# Boss_HM-2.net
KiCad netlist of a schematic drawn in EAGLE
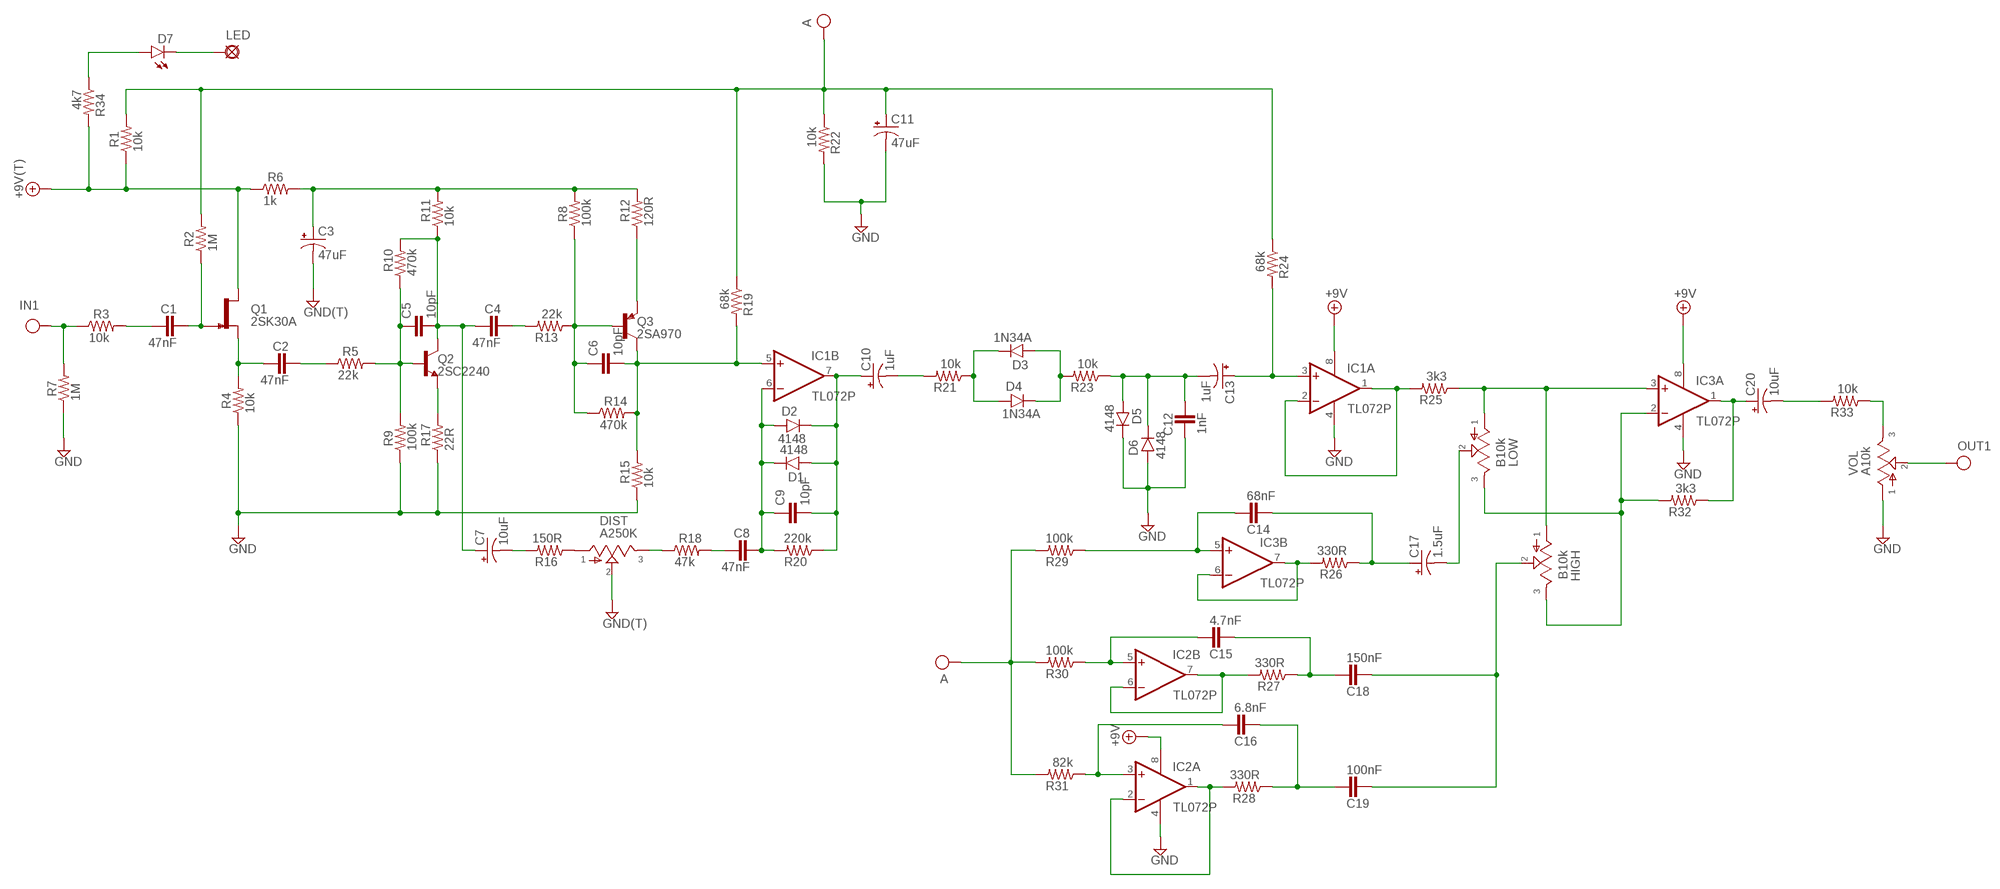
[diagram p0: schematic, sheet 1]

(export (version "E")
  (design (tool "Eeschema 10.0.6"))
  (components
    (comp (ref "+9V1")
      (value "+9V(T)")
      (footprint "eagle-import:SQUARE")
      (libsource (lib "eagle-import") (part "+9V(T)"))
    )
    (comp (ref "C1")
      (value "47nF")
      (footprint "eagle-import:072X025")
      (libsource (lib "eagle-import") (part "072X0252"))
    )
    (comp (ref "C2")
      (value "47nF")
      (footprint "eagle-import:072X025")
      (libsource (lib "eagle-import") (part "072X0252"))
    )
    (comp (ref "C3")
      (value "47uF")
      (footprint "eagle-import:050_020_1")
      (libsource (lib "eagle-import") (part "0501"))
    )
    (comp (ref "C4")
      (value "47nF")
      (footprint "eagle-import:072X025")
      (libsource (lib "eagle-import") (part "072X0252"))
    )
    (comp (ref "C5")
      (value "10pF")
      (footprint "eagle-import:050X030_025")
      (libsource (lib "eagle-import") (part "050X030_0251"))
    )
    (comp (ref "C6")
      (value "10pF")
      (footprint "eagle-import:050X030_025")
      (libsource (lib "eagle-import") (part "050X030_0251"))
    )
    (comp (ref "C7")
      (value "10uF")
      (footprint "eagle-import:050_020_1")
      (libsource (lib "eagle-import") (part "0501"))
    )
    (comp (ref "C8")
      (value "47nF")
      (footprint "eagle-import:072X025")
      (libsource (lib "eagle-import") (part "072X0252"))
    )
    (comp (ref "C9")
      (value "10pF")
      (footprint "eagle-import:050X030_025")
      (libsource (lib "eagle-import") (part "050X030_0251"))
    )
    (comp (ref "C10")
      (value "1uF")
      (footprint "eagle-import:050_020_1")
      (libsource (lib "eagle-import") (part "0501"))
    )
    (comp (ref "C11")
      (value "47uF")
      (footprint "eagle-import:050_020_1")
      (libsource (lib "eagle-import") (part "0501"))
    )
    (comp (ref "C12")
      (value "1nF")
      (footprint "eagle-import:072X025")
      (libsource (lib "eagle-import") (part "072X0252"))
    )
    (comp (ref "C13")
      (value "1uF")
      (footprint "eagle-import:050_020_1")
      (libsource (lib "eagle-import") (part "0501"))
    )
    (comp (ref "C14")
      (value "68nF")
      (footprint "eagle-import:072X025")
      (libsource (lib "eagle-import") (part "072X0252"))
    )
    (comp (ref "C15")
      (value "4.7nF")
      (footprint "eagle-import:072X025")
      (libsource (lib "eagle-import") (part "072X0252"))
    )
    (comp (ref "C16")
      (value "6.8nF")
      (footprint "eagle-import:072X025")
      (libsource (lib "eagle-import") (part "072X0252"))
    )
    (comp (ref "C17")
      (value "1.5uF")
      (footprint "eagle-import:050_020_1")
      (libsource (lib "eagle-import") (part "0501"))
    )
    (comp (ref "C18")
      (value "150nF")
      (footprint "eagle-import:072X025")
      (libsource (lib "eagle-import") (part "072X0252"))
    )
    (comp (ref "C19")
      (value "100nF")
      (footprint "eagle-import:072X025")
      (libsource (lib "eagle-import") (part "072X0252"))
    )
    (comp (ref "C20")
      (value "10uF")
      (footprint "eagle-import:050_020_1")
      (libsource (lib "eagle-import") (part "0501"))
    )
    (comp (ref "D1")
      (value "4148")
      (footprint "eagle-import:DO35-3")
      (libsource (lib "eagle-import") (part "1N4148-3"))
    )
    (comp (ref "D2")
      (value "4148")
      (footprint "eagle-import:DO35-3")
      (libsource (lib "eagle-import") (part "1N4148-3"))
    )
    (comp (ref "D3")
      (value "1N34A")
      (footprint "eagle-import:DO07")
      (libsource (lib "eagle-import") (part "DO07"))
    )
    (comp (ref "D4")
      (value "1N34A")
      (footprint "eagle-import:DO07")
      (libsource (lib "eagle-import") (part "DO07"))
    )
    (comp (ref "D5")
      (value "4148")
      (footprint "eagle-import:DO35-3")
      (libsource (lib "eagle-import") (part "1N4148-3"))
    )
    (comp (ref "D6")
      (value "4148")
      (footprint "eagle-import:DO35-3")
      (libsource (lib "eagle-import") (part "1N4148-3"))
    )
    (comp (ref "D7")
      (value "LED3MM")
      (footprint "eagle-import:LED3MM")
      (libsource (lib "eagle-import") (part "LED3MM"))
    )
    (comp (ref "DIST")
      (value "A250K")
      (footprint "eagle-import:16MM_PCB_PADS")
      (libsource (lib "eagle-import") (part "POT16MM_PCB_PADS"))
    )
    (comp (ref "GND1")
      (value "GND(T)")
      (footprint "eagle-import:SQUARE")
      (libsource (lib "eagle-import") (part "GND(T)"))
    )
    (comp (ref "GND2")
      (value "GND(T)")
      (footprint "eagle-import:SQUARE")
      (libsource (lib "eagle-import") (part "GND(T)"))
    )
    (comp (ref "HIGH")
      (value "B10k")
      (footprint "eagle-import:16MM_PCB_PADS")
      (libsource (lib "eagle-import") (part "POT16MM_PCB_PADS"))
    )
    (comp (ref "IC1")
      (value "TL072P")
      (footprint "eagle-import:DIL08")
      (libsource (lib "eagle-import") (part "TL072P"))
    )
    (comp (ref "IC2")
      (value "TL072P")
      (footprint "eagle-import:DIL08")
      (libsource (lib "eagle-import") (part "TL072P"))
    )
    (comp (ref "IC3")
      (value "TL072P")
      (footprint "eagle-import:DIL08")
      (libsource (lib "eagle-import") (part "TL072P"))
    )
    (comp (ref "IN1")
      (value "IN(T)")
      (footprint "eagle-import:SQUARE")
      (libsource (lib "eagle-import") (part "IN(T)"))
    )
    (comp (ref "LED")
      (value "PAD")
      (footprint "eagle-import:SQUARE")
      (libsource (lib "eagle-import") (part "PAD"))
    )
    (comp (ref "LOW")
      (value "B10k")
      (footprint "eagle-import:16MM_PCB_PADS")
      (libsource (lib "eagle-import") (part "POT16MM_PCB_PADS"))
    )
    (comp (ref "OUT1")
      (value "OUT(T)")
      (footprint "eagle-import:SQUARE")
      (libsource (lib "eagle-import") (part "OUT(T)"))
    )
    (comp (ref "Q1")
      (value "2SK30A")
      (footprint "eagle-import:TO92-")
      (libsource (lib "eagle-import") (part "2SK30A"))
    )
    (comp (ref "Q2")
      (value "2SC2240")
      (footprint "eagle-import:TO92-")
      (libsource (lib "eagle-import") (part "2N5089"))
    )
    (comp (ref "Q3")
      (value "2SA970")
      (footprint "eagle-import:TO92-")
      (libsource (lib "eagle-import") (part "2SA733"))
    )
    (comp (ref "R1")
      (value "10k")
      (footprint "eagle-import:R0207_3")
      (libsource (lib "eagle-import") (part "6MM.3"))
    )
    (comp (ref "R2")
      (value "1M")
      (footprint "eagle-import:R0207_3")
      (libsource (lib "eagle-import") (part "6MM.3"))
    )
    (comp (ref "R3")
      (value "10k")
      (footprint "eagle-import:R0207_3")
      (libsource (lib "eagle-import") (part "6MM.3"))
    )
    (comp (ref "R4")
      (value "10k")
      (footprint "eagle-import:R0207_3")
      (libsource (lib "eagle-import") (part "6MM.3"))
    )
    (comp (ref "R5")
      (value "22k")
      (footprint "eagle-import:R0207_3")
      (libsource (lib "eagle-import") (part "6MM.3"))
    )
    (comp (ref "R6")
      (value "1k")
      (footprint "eagle-import:R0207_3")
      (libsource (lib "eagle-import") (part "6MM.3"))
    )
    (comp (ref "R7")
      (value "1M")
      (footprint "eagle-import:R0207_3")
      (libsource (lib "eagle-import") (part "6MM.3"))
    )
    (comp (ref "R8")
      (value "100k")
      (footprint "eagle-import:R0207_3")
      (libsource (lib "eagle-import") (part "6MM.3"))
    )
    (comp (ref "R9")
      (value "100k")
      (footprint "eagle-import:R0207_3")
      (libsource (lib "eagle-import") (part "6MM.3"))
    )
    (comp (ref "R10")
      (value "470k")
      (footprint "eagle-import:R0207_3")
      (libsource (lib "eagle-import") (part "6MM.3"))
    )
    (comp (ref "R11")
      (value "10k")
      (footprint "eagle-import:R0207_3")
      (libsource (lib "eagle-import") (part "6MM.3"))
    )
    (comp (ref "R12")
      (value "120R")
      (footprint "eagle-import:R0207_3")
      (libsource (lib "eagle-import") (part "6MM.3"))
    )
    (comp (ref "R13")
      (value "22k")
      (footprint "eagle-import:R0207_3")
      (libsource (lib "eagle-import") (part "6MM.3"))
    )
    (comp (ref "R14")
      (value "470k")
      (footprint "eagle-import:R0207_3")
      (libsource (lib "eagle-import") (part "6MM.3"))
    )
    (comp (ref "R15")
      (value "10k")
      (footprint "eagle-import:R0207_3")
      (libsource (lib "eagle-import") (part "6MM.3"))
    )
    (comp (ref "R16")
      (value "150R")
      (footprint "eagle-import:R0207_3")
      (libsource (lib "eagle-import") (part "6MM.3"))
    )
    (comp (ref "R17")
      (value "22R")
      (footprint "eagle-import:R0207_3")
      (libsource (lib "eagle-import") (part "6MM.3"))
    )
    (comp (ref "R18")
      (value "47k")
      (footprint "eagle-import:R0207_3")
      (libsource (lib "eagle-import") (part "6MM.3"))
    )
    (comp (ref "R19")
      (value "68k")
      (footprint "eagle-import:R0207_3")
      (libsource (lib "eagle-import") (part "6MM.3"))
    )
    (comp (ref "R20")
      (value "220k")
      (footprint "eagle-import:R0207_3")
      (libsource (lib "eagle-import") (part "6MM.3"))
    )
    (comp (ref "R21")
      (value "10k")
      (footprint "eagle-import:R0207_3")
      (libsource (lib "eagle-import") (part "6MM.3"))
    )
    (comp (ref "R22")
      (value "10k")
      (footprint "eagle-import:R0207_3")
      (libsource (lib "eagle-import") (part "6MM.3"))
    )
    (comp (ref "R23")
      (value "10k")
      (footprint "eagle-import:R0207_3")
      (libsource (lib "eagle-import") (part "6MM.3"))
    )
    (comp (ref "R24")
      (value "68k")
      (footprint "eagle-import:R0207_3")
      (libsource (lib "eagle-import") (part "6MM.3"))
    )
    (comp (ref "R25")
      (value "3k3")
      (footprint "eagle-import:R0207_3")
      (libsource (lib "eagle-import") (part "6MM.3"))
    )
    (comp (ref "R26")
      (value "330R")
      (footprint "eagle-import:R0207_3")
      (libsource (lib "eagle-import") (part "6MM.3"))
    )
    (comp (ref "R27")
      (value "330R")
      (footprint "eagle-import:R0207_3")
      (libsource (lib "eagle-import") (part "6MM.3"))
    )
    (comp (ref "R28")
      (value "330R")
      (footprint "eagle-import:R0207_3")
      (libsource (lib "eagle-import") (part "6MM.3"))
    )
    (comp (ref "R29")
      (value "100k")
      (footprint "eagle-import:R0207_3")
      (libsource (lib "eagle-import") (part "6MM.3"))
    )
    (comp (ref "R30")
      (value "100k")
      (footprint "eagle-import:R0207_3")
      (libsource (lib "eagle-import") (part "6MM.3"))
    )
    (comp (ref "R31")
      (value "82k")
      (footprint "eagle-import:R0207_3")
      (libsource (lib "eagle-import") (part "6MM.3"))
    )
    (comp (ref "R32")
      (value "3k3")
      (footprint "eagle-import:R0207_3")
      (libsource (lib "eagle-import") (part "6MM.3"))
    )
    (comp (ref "R33")
      (value "10k")
      (footprint "eagle-import:R0207_3")
      (libsource (lib "eagle-import") (part "6MM.3"))
    )
    (comp (ref "R34")
      (value "4k7")
      (footprint "eagle-import:R0207_3")
      (libsource (lib "eagle-import") (part "6MM.3"))
    )
    (comp (ref "VOL")
      (value "A10k")
      (footprint "eagle-import:16MM_PCB_PADS")
      (libsource (lib "eagle-import") (part "POT16MM_PCB_PADS"))
    )
  )
  (nets
    (net (code "1") (name "+9V") (class "Default")
      (node (ref "+9V1") (pin "1") (pinfunction "+9V_1") (pintype "power_in"))
      (node (ref "IC1") (pin "8") (pinfunction "V+_8") (pintype "power_in"))
      (node (ref "IC2") (pin "8") (pinfunction "V+_8") (pintype "power_in"))
      (node (ref "IC3") (pin "8") (pinfunction "V+_8") (pintype "power_in"))
      (node (ref "Q1") (pin "3") (pinfunction "D_3") (pintype "passive"))
      (node (ref "R1") (pin "1") (pinfunction "1_1") (pintype "passive"))
      (node (ref "R34") (pin "2") (pinfunction "2_2") (pintype "passive"))
      (node (ref "R6") (pin "1") (pinfunction "1_1") (pintype "passive"))
    )
    (net (code "2") (name "A") (class "Default")
      (node (ref "C11") (pin "+") (pinfunction "+_+") (pintype "passive"))
      (node (ref "R1") (pin "2") (pinfunction "2_2") (pintype "passive"))
      (node (ref "R19") (pin "1") (pinfunction "1_1") (pintype "passive"))
      (node (ref "R2") (pin "2") (pinfunction "2_2") (pintype "passive"))
      (node (ref "R22") (pin "1") (pinfunction "1_1") (pintype "passive"))
      (node (ref "R24") (pin "1") (pinfunction "1_1") (pintype "passive"))
      (node (ref "R29") (pin "2") (pinfunction "2_2") (pintype "passive"))
      (node (ref "R30") (pin "2") (pinfunction "2_2") (pintype "passive"))
      (node (ref "R31") (pin "2") (pinfunction "2_2") (pintype "passive"))
    )
    (net (code "3") (name "GND") (class "Default")
      (node (ref "C11") (pin "-") (pinfunction "-_-") (pintype "passive"))
      (node (ref "C12") (pin "1") (pinfunction "1_1") (pintype "passive"))
      (node (ref "C3") (pin "-") (pinfunction "-_-") (pintype "passive"))
      (node (ref "D5") (pin "C") (pinfunction "C_C") (pintype "passive"))
      (node (ref "D6") (pin "A") (pinfunction "A_A") (pintype "passive"))
      (node (ref "DIST") (pin "2") (pinfunction "2_2") (pintype "passive"))
      (node (ref "GND1") (pin "1") (pinfunction "GND_1") (pintype "power_in"))
      (node (ref "GND2") (pin "1") (pinfunction "GND_1") (pintype "power_in"))
      (node (ref "IC1") (pin "4") (pinfunction "V-_4") (pintype "power_in"))
      (node (ref "IC2") (pin "4") (pinfunction "V-_4") (pintype "power_in"))
      (node (ref "IC3") (pin "4") (pinfunction "V-_4") (pintype "power_in"))
      (node (ref "R15") (pin "1") (pinfunction "1_1") (pintype "passive"))
      (node (ref "R17") (pin "1") (pinfunction "1_1") (pintype "passive"))
      (node (ref "R22") (pin "2") (pinfunction "2_2") (pintype "passive"))
      (node (ref "R4") (pin "1") (pinfunction "1_1") (pintype "passive"))
      (node (ref "R7") (pin "1") (pinfunction "1_1") (pintype "passive"))
      (node (ref "R9") (pin "1") (pinfunction "1_1") (pintype "passive"))
      (node (ref "VOL") (pin "1") (pinfunction "1_1") (pintype "passive"))
    )
    (net (code "4") (name "IN(T)") (class "Default")
      (node (ref "IN1") (pin "1") (pinfunction "IN_1") (pintype "power_in"))
      (node (ref "R3") (pin "1") (pinfunction "1_1") (pintype "passive"))
      (node (ref "R7") (pin "2") (pinfunction "2_2") (pintype "passive"))
    )
    (net (code "5") (name "Net-(C1-Pad1)") (class "Default")
      (node (ref "C1") (pin "1") (pinfunction "1_1") (pintype "passive"))
      (node (ref "R3") (pin "2") (pinfunction "2_2") (pintype "passive"))
    )
    (net (code "6") (name "Net-(C2-Pad2)") (class "Default")
      (node (ref "C2") (pin "2") (pinfunction "2_2") (pintype "passive"))
      (node (ref "R5") (pin "1") (pinfunction "1_1") (pintype "passive"))
    )
    (net (code "7") (name "Net-(C3-Pad+)") (class "Default")
      (node (ref "C3") (pin "+") (pinfunction "+_+") (pintype "passive"))
      (node (ref "R11") (pin "2") (pinfunction "2_2") (pintype "passive"))
      (node (ref "R12") (pin "2") (pinfunction "2_2") (pintype "passive"))
      (node (ref "R6") (pin "2") (pinfunction "2_2") (pintype "passive"))
      (node (ref "R8") (pin "2") (pinfunction "2_2") (pintype "passive"))
    )
    (net (code "8") (name "Net-(C4-Pad2)") (class "Default")
      (node (ref "C4") (pin "2") (pinfunction "2_2") (pintype "passive"))
      (node (ref "R13") (pin "2") (pinfunction "2_2") (pintype "passive"))
    )
    (net (code "9") (name "Net-(C7-Pad-)") (class "Default")
      (node (ref "C7") (pin "-") (pinfunction "-_-") (pintype "passive"))
      (node (ref "R16") (pin "2") (pinfunction "2_2") (pintype "passive"))
    )
    (net (code "10") (name "Net-(C8-Pad1)") (class "Default")
      (node (ref "C8") (pin "1") (pinfunction "1_1") (pintype "passive"))
      (node (ref "R18") (pin "2") (pinfunction "2_2") (pintype "passive"))
    )
    (net (code "11") (name "Net-(C10-Pad-)") (class "Default")
      (node (ref "C10") (pin "-") (pinfunction "-_-") (pintype "passive"))
      (node (ref "R21") (pin "2") (pinfunction "2_2") (pintype "passive"))
    )
    (net (code "12") (name "Net-(C12-Pad2)") (class "Default")
      (node (ref "C12") (pin "2") (pinfunction "2_2") (pintype "passive"))
      (node (ref "C13") (pin "-") (pinfunction "-_-") (pintype "passive"))
      (node (ref "D5") (pin "A") (pinfunction "A_A") (pintype "passive"))
      (node (ref "D6") (pin "C") (pinfunction "C_C") (pintype "passive"))
      (node (ref "R23") (pin "1") (pinfunction "1_1") (pintype "passive"))
    )
    (net (code "13") (name "Net-(C14-Pad1)") (class "Default")
      (node (ref "C14") (pin "1") (pinfunction "1_1") (pintype "passive"))
      (node (ref "C17") (pin "+") (pinfunction "+_+") (pintype "passive"))
      (node (ref "R26") (pin "1") (pinfunction "1_1") (pintype "passive"))
    )
    (net (code "14") (name "Net-(C15-Pad1)") (class "Default")
      (node (ref "C15") (pin "1") (pinfunction "1_1") (pintype "passive"))
      (node (ref "C18") (pin "2") (pinfunction "2_2") (pintype "passive"))
      (node (ref "R27") (pin "1") (pinfunction "1_1") (pintype "passive"))
    )
    (net (code "15") (name "Net-(C16-Pad1)") (class "Default")
      (node (ref "C16") (pin "1") (pinfunction "1_1") (pintype "passive"))
      (node (ref "C19") (pin "2") (pinfunction "2_2") (pintype "passive"))
      (node (ref "R28") (pin "1") (pinfunction "1_1") (pintype "passive"))
    )
    (net (code "16") (name "Net-(C17-Pad-)") (class "Default")
      (node (ref "C17") (pin "-") (pinfunction "-_-") (pintype "passive"))
      (node (ref "LOW") (pin "2") (pinfunction "2_2") (pintype "passive"))
    )
    (net (code "17") (name "Net-(C18-Pad1)") (class "Default")
      (node (ref "C18") (pin "1") (pinfunction "1_1") (pintype "passive"))
      (node (ref "C19") (pin "1") (pinfunction "1_1") (pintype "passive"))
      (node (ref "HIGH") (pin "2") (pinfunction "2_2") (pintype "passive"))
    )
    (net (code "18") (name "Net-(C20-Pad-)") (class "Default")
      (node (ref "C20") (pin "-") (pinfunction "-_-") (pintype "passive"))
      (node (ref "R33") (pin "2") (pinfunction "2_2") (pintype "passive"))
    )
    (net (code "19") (name "Net-(D3-PadA)") (class "Default")
      (node (ref "D3") (pin "A") (pinfunction "A_A") (pintype "passive"))
      (node (ref "D4") (pin "C") (pinfunction "C_C") (pintype "passive"))
      (node (ref "R23") (pin "2") (pinfunction "2_2") (pintype "passive"))
    )
    (net (code "20") (name "Net-(D3-PadC)") (class "Default")
      (node (ref "D3") (pin "C") (pinfunction "C_C") (pintype "passive"))
      (node (ref "D4") (pin "A") (pinfunction "A_A") (pintype "passive"))
      (node (ref "R21") (pin "1") (pinfunction "1_1") (pintype "passive"))
    )
    (net (code "21") (name "Net-(D7-C)") (class "Default")
      (node (ref "D7") (pin "K") (pinfunction "C_K") (pintype "passive"))
      (node (ref "LED") (pin "1") (pinfunction "PAD_1") (pintype "passive"))
    )
    (net (code "22") (name "Net-(D7-PadA)") (class "Default")
      (node (ref "D7") (pin "A") (pinfunction "A_A") (pintype "passive"))
      (node (ref "R34") (pin "1") (pinfunction "1_1") (pintype "passive"))
    )
    (net (code "23") (name "Net-(DIST-Pad1)") (class "Default")
      (node (ref "DIST") (pin "1") (pinfunction "1_1") (pintype "passive"))
      (node (ref "R16") (pin "1") (pinfunction "1_1") (pintype "passive"))
    )
    (net (code "24") (name "Net-(DIST-Pad3)") (class "Default")
      (node (ref "DIST") (pin "3") (pinfunction "3_3") (pintype "passive"))
      (node (ref "R18") (pin "1") (pinfunction "1_1") (pintype "passive"))
    )
    (net (code "25") (name "Net-(IC1A-+IN)") (class "Default")
      (node (ref "C13") (pin "+") (pinfunction "+_+") (pintype "passive"))
      (node (ref "IC1") (pin "3") (pinfunction "+IN_3") (pintype "input"))
      (node (ref "R24") (pin "2") (pinfunction "2_2") (pintype "passive"))
    )
    (net (code "26") (name "Net-(IC1A--IN)") (class "Default")
      (node (ref "IC1") (pin "1") (pinfunction "OUT_1") (pintype "output"))
      (node (ref "IC1") (pin "2") (pinfunction "-IN_2") (pintype "input"))
      (node (ref "R25") (pin "2") (pinfunction "2_2") (pintype "passive"))
    )
    (net (code "27") (name "Net-(IC1B-+IN)") (class "Default")
      (node (ref "C6") (pin "2") (pinfunction "2_2") (pintype "passive"))
      (node (ref "IC1") (pin "5") (pinfunction "+IN_5") (pintype "input"))
      (node (ref "Q3") (pin "2") (pinfunction "C_2") (pintype "passive"))
      (node (ref "R14") (pin "2") (pinfunction "2_2") (pintype "passive"))
      (node (ref "R15") (pin "2") (pinfunction "2_2") (pintype "passive"))
      (node (ref "R19") (pin "2") (pinfunction "2_2") (pintype "passive"))
    )
    (net (code "28") (name "Net-(IC1B--IN)") (class "Default")
      (node (ref "C8") (pin "2") (pinfunction "2_2") (pintype "passive"))
      (node (ref "C9") (pin "1") (pinfunction "1_1") (pintype "passive"))
      (node (ref "D1") (pin "C") (pinfunction "C_C") (pintype "passive"))
      (node (ref "D2") (pin "A") (pinfunction "A_A") (pintype "passive"))
      (node (ref "IC1") (pin "6") (pinfunction "-IN_6") (pintype "input"))
      (node (ref "R20") (pin "2") (pinfunction "2_2") (pintype "passive"))
    )
    (net (code "29") (name "Net-(IC1B-OUT)") (class "Default")
      (node (ref "C10") (pin "+") (pinfunction "+_+") (pintype "passive"))
      (node (ref "C9") (pin "2") (pinfunction "2_2") (pintype "passive"))
      (node (ref "D1") (pin "A") (pinfunction "A_A") (pintype "passive"))
      (node (ref "D2") (pin "C") (pinfunction "C_C") (pintype "passive"))
      (node (ref "IC1") (pin "7") (pinfunction "OUT_7") (pintype "output"))
      (node (ref "R20") (pin "1") (pinfunction "1_1") (pintype "passive"))
    )
    (net (code "30") (name "Net-(IC2A-+IN)") (class "Default")
      (node (ref "C16") (pin "2") (pinfunction "2_2") (pintype "passive"))
      (node (ref "IC2") (pin "3") (pinfunction "+IN_3") (pintype "input"))
      (node (ref "R31") (pin "1") (pinfunction "1_1") (pintype "passive"))
    )
    (net (code "31") (name "Net-(IC2A--IN)") (class "Default")
      (node (ref "IC2") (pin "1") (pinfunction "OUT_1") (pintype "output"))
      (node (ref "IC2") (pin "2") (pinfunction "-IN_2") (pintype "input"))
      (node (ref "R28") (pin "2") (pinfunction "2_2") (pintype "passive"))
    )
    (net (code "32") (name "Net-(IC2B-+IN)") (class "Default")
      (node (ref "C15") (pin "2") (pinfunction "2_2") (pintype "passive"))
      (node (ref "IC2") (pin "5") (pinfunction "+IN_5") (pintype "input"))
      (node (ref "R30") (pin "1") (pinfunction "1_1") (pintype "passive"))
    )
    (net (code "33") (name "Net-(IC2B--IN)") (class "Default")
      (node (ref "IC2") (pin "6") (pinfunction "-IN_6") (pintype "input"))
      (node (ref "IC2") (pin "7") (pinfunction "OUT_7") (pintype "output"))
      (node (ref "R27") (pin "2") (pinfunction "2_2") (pintype "passive"))
    )
    (net (code "34") (name "Net-(IC3A-+IN)") (class "Default")
      (node (ref "HIGH") (pin "1") (pinfunction "1_1") (pintype "passive"))
      (node (ref "IC3") (pin "3") (pinfunction "+IN_3") (pintype "input"))
      (node (ref "LOW") (pin "1") (pinfunction "1_1") (pintype "passive"))
      (node (ref "R25") (pin "1") (pinfunction "1_1") (pintype "passive"))
    )
    (net (code "35") (name "Net-(IC3A--IN)") (class "Default")
      (node (ref "HIGH") (pin "3") (pinfunction "3_3") (pintype "passive"))
      (node (ref "IC3") (pin "2") (pinfunction "-IN_2") (pintype "input"))
      (node (ref "LOW") (pin "3") (pinfunction "3_3") (pintype "passive"))
      (node (ref "R32") (pin "2") (pinfunction "2_2") (pintype "passive"))
    )
    (net (code "36") (name "Net-(IC3A-OUT)") (class "Default")
      (node (ref "C20") (pin "+") (pinfunction "+_+") (pintype "passive"))
      (node (ref "IC3") (pin "1") (pinfunction "OUT_1") (pintype "output"))
      (node (ref "R32") (pin "1") (pinfunction "1_1") (pintype "passive"))
    )
    (net (code "37") (name "Net-(IC3B-+IN)") (class "Default")
      (node (ref "C14") (pin "2") (pinfunction "2_2") (pintype "passive"))
      (node (ref "IC3") (pin "5") (pinfunction "+IN_5") (pintype "input"))
      (node (ref "R29") (pin "1") (pinfunction "1_1") (pintype "passive"))
    )
    (net (code "38") (name "Net-(IC3B--IN)") (class "Default")
      (node (ref "IC3") (pin "6") (pinfunction "-IN_6") (pintype "input"))
      (node (ref "IC3") (pin "7") (pinfunction "OUT_7") (pintype "output"))
      (node (ref "R26") (pin "2") (pinfunction "2_2") (pintype "passive"))
    )
    (net (code "39") (name "Net-(Q1-G)") (class "Default")
      (node (ref "C1") (pin "2") (pinfunction "2_2") (pintype "passive"))
      (node (ref "Q1") (pin "2") (pinfunction "G_2") (pintype "passive"))
      (node (ref "R2") (pin "1") (pinfunction "1_1") (pintype "passive"))
    )
    (net (code "40") (name "Net-(Q1-S)") (class "Default")
      (node (ref "C2") (pin "1") (pinfunction "1_1") (pintype "passive"))
      (node (ref "Q1") (pin "1") (pinfunction "S_1") (pintype "passive"))
      (node (ref "R4") (pin "2") (pinfunction "2_2") (pintype "passive"))
    )
    (net (code "41") (name "Net-(Q2-B)") (class "Default")
      (node (ref "C5") (pin "1") (pinfunction "1_1") (pintype "passive"))
      (node (ref "Q2") (pin "2") (pinfunction "B_2") (pintype "passive"))
      (node (ref "R10") (pin "1") (pinfunction "1_1") (pintype "passive"))
      (node (ref "R5") (pin "2") (pinfunction "2_2") (pintype "passive"))
      (node (ref "R9") (pin "2") (pinfunction "2_2") (pintype "passive"))
    )
    (net (code "42") (name "Net-(Q2-C)") (class "Default")
      (node (ref "C4") (pin "1") (pinfunction "1_1") (pintype "passive"))
      (node (ref "C5") (pin "2") (pinfunction "2_2") (pintype "passive"))
      (node (ref "C7") (pin "+") (pinfunction "+_+") (pintype "passive"))
      (node (ref "Q2") (pin "1") (pinfunction "C_1") (pintype "passive"))
      (node (ref "R10") (pin "2") (pinfunction "2_2") (pintype "passive"))
      (node (ref "R11") (pin "1") (pinfunction "1_1") (pintype "passive"))
    )
    (net (code "43") (name "Net-(Q2-E)") (class "Default")
      (node (ref "Q2") (pin "3") (pinfunction "E_3") (pintype "passive"))
      (node (ref "R17") (pin "2") (pinfunction "2_2") (pintype "passive"))
    )
    (net (code "44") (name "Net-(Q3-B)") (class "Default")
      (node (ref "C6") (pin "1") (pinfunction "1_1") (pintype "passive"))
      (node (ref "Q3") (pin "1") (pinfunction "B_1") (pintype "passive"))
      (node (ref "R13") (pin "1") (pinfunction "1_1") (pintype "passive"))
      (node (ref "R14") (pin "1") (pinfunction "1_1") (pintype "passive"))
      (node (ref "R8") (pin "1") (pinfunction "1_1") (pintype "passive"))
    )
    (net (code "45") (name "Net-(Q3-E)") (class "Default")
      (node (ref "Q3") (pin "3") (pinfunction "E_3") (pintype "passive"))
      (node (ref "R12") (pin "1") (pinfunction "1_1") (pintype "passive"))
    )
    (net (code "46") (name "Net-(R33-Pad1)") (class "Default")
      (node (ref "R33") (pin "1") (pinfunction "1_1") (pintype "passive"))
      (node (ref "VOL") (pin "3") (pinfunction "3_3") (pintype "passive"))
    )
    (net (code "47") (name "OUT(T)") (class "Default")
      (node (ref "OUT1") (pin "1") (pinfunction "OUT_1") (pintype "power_in"))
      (node (ref "VOL") (pin "2") (pinfunction "2_2") (pintype "passive"))
    )
  )
)
